# d_00_e_00.net
KiCad netlist of a schematic drawn in EasyEDA
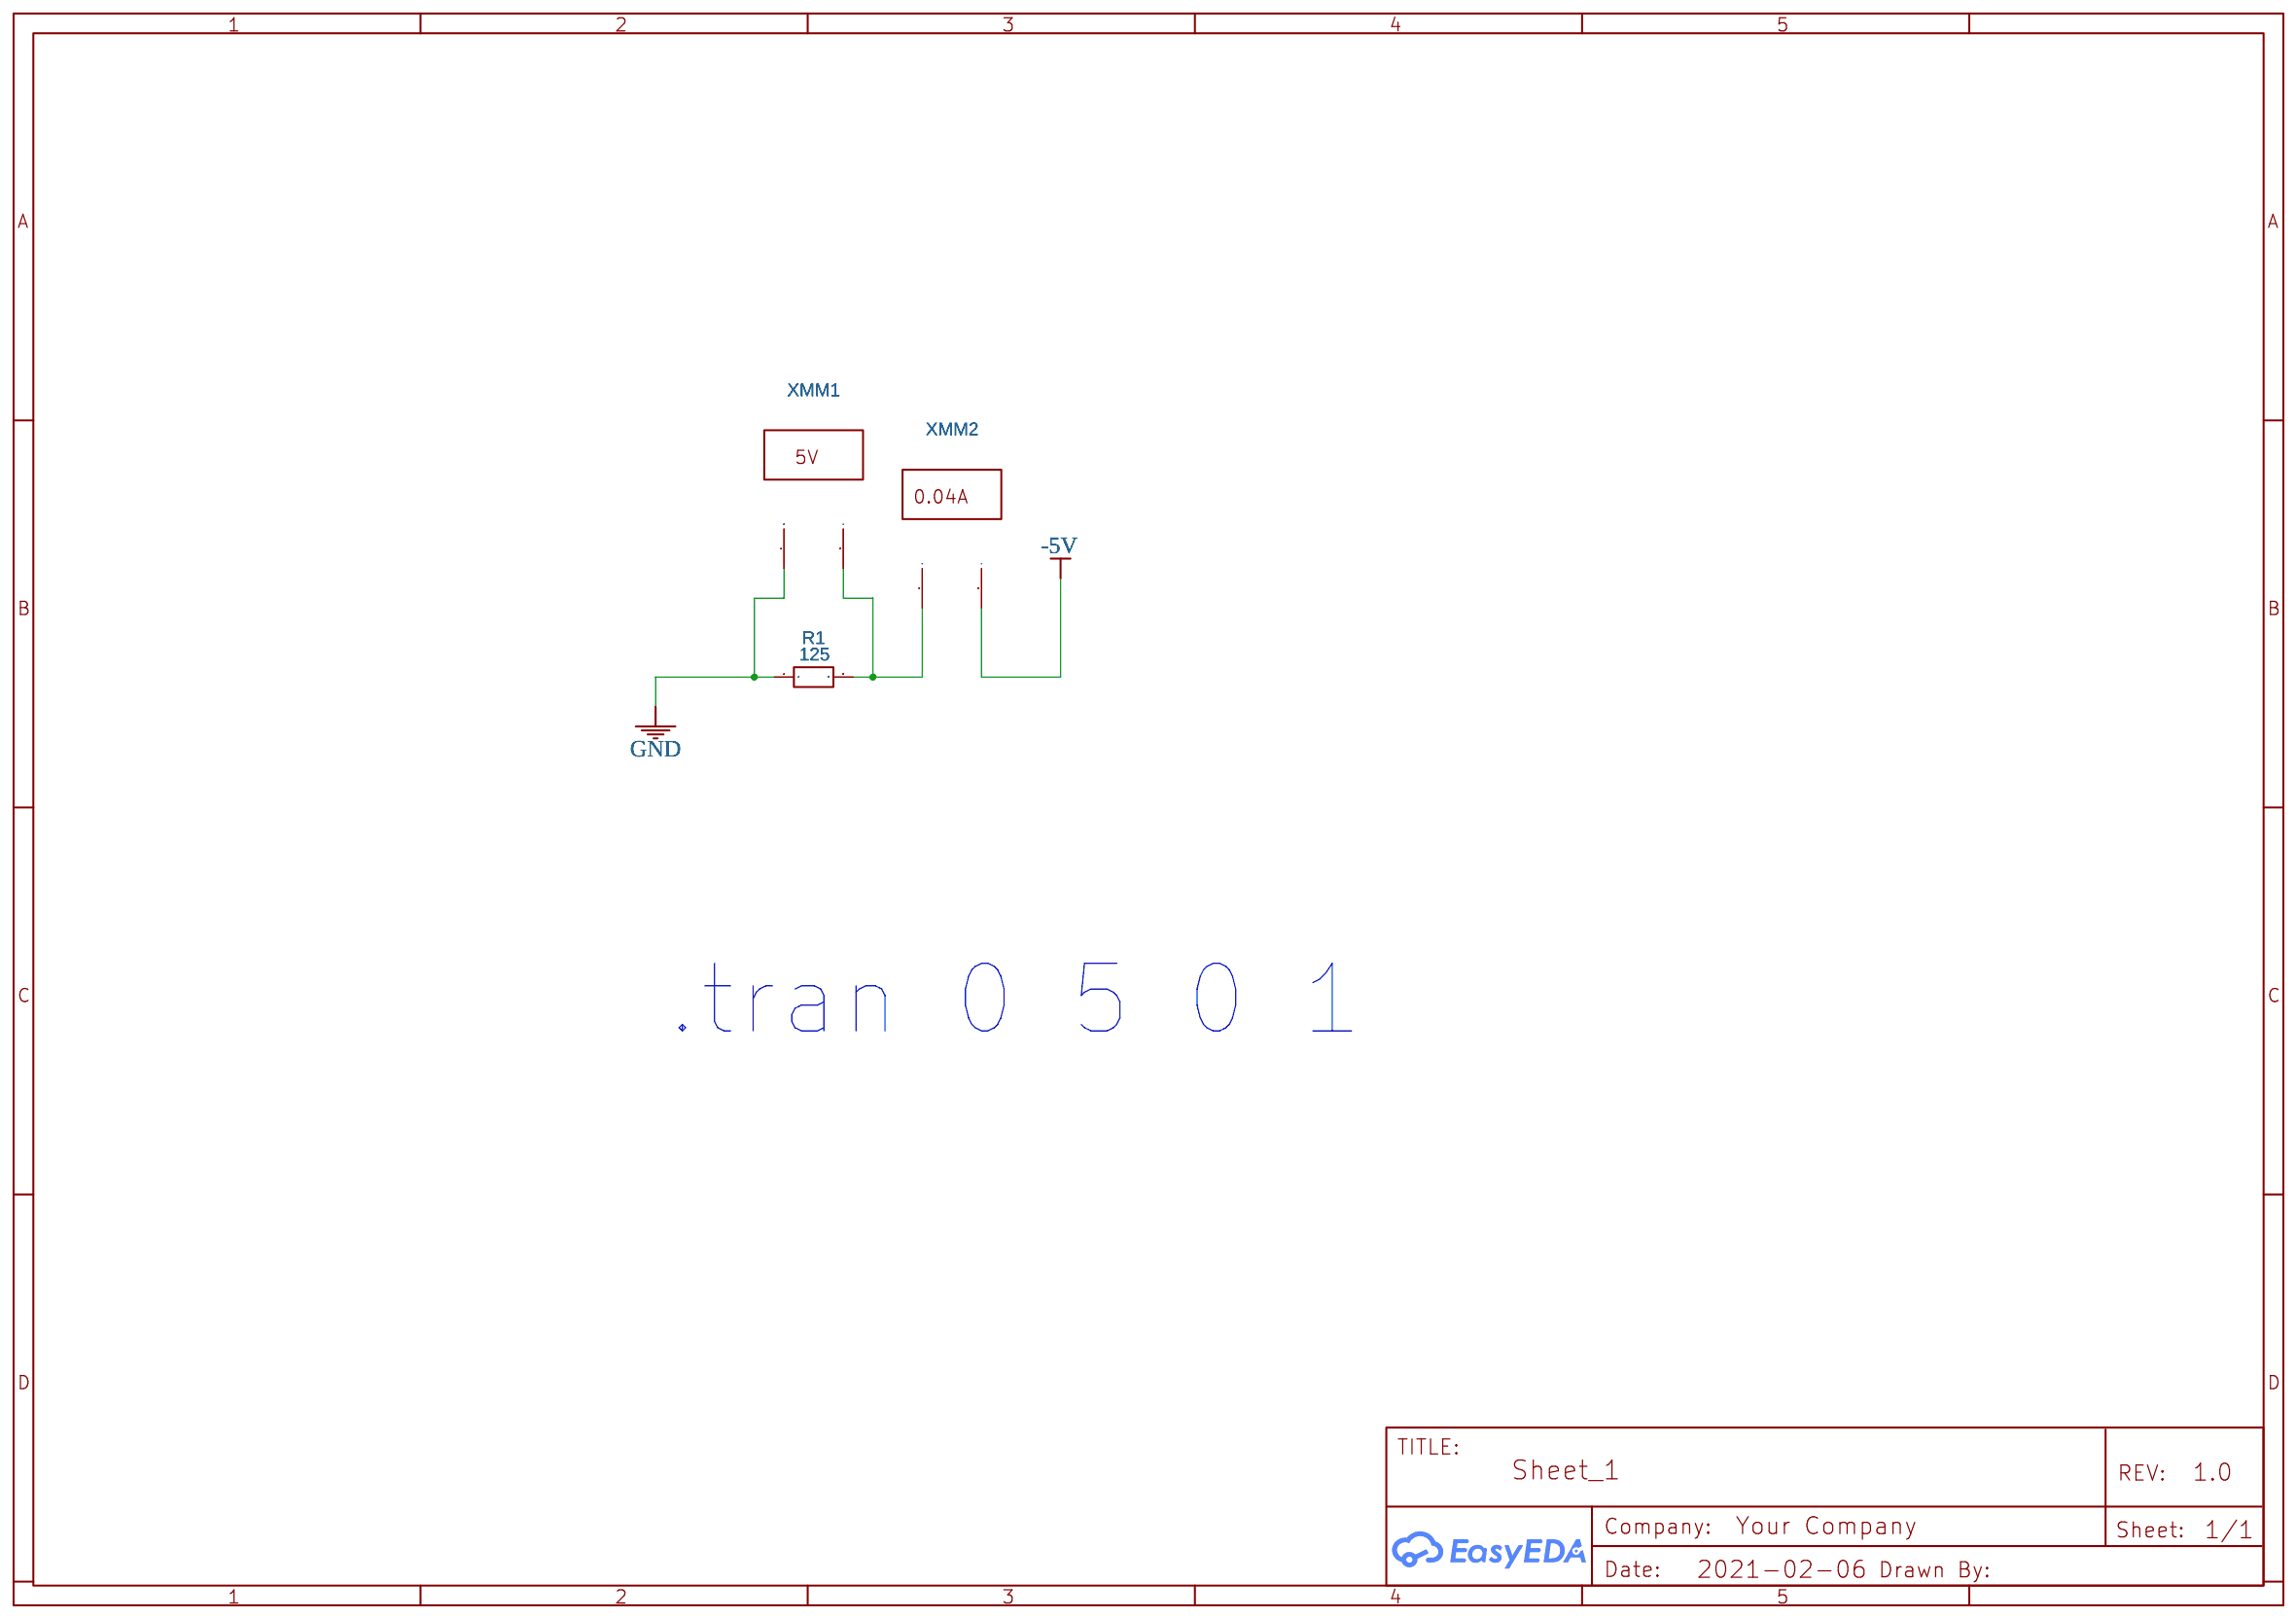
[diagram p0: schematic sheet]

(export (version "E")
  (design (tool "Eeschema 10.0.6"))
  (components
    (comp (ref "R1") (value "125") (libsource (lib "") (part "R_0603_EU")))
    (comp (ref "XMM1") (value "Multimeter") (libsource (lib "") (part "MULTIMETER")))
    (comp (ref "XMM2") (value "Multimeter") (libsource (lib "") (part "MULTIMETER_1")))
  )
  (nets
    (net (code "1") (name "-5V") (class "Default")
      (node (ref "XMM2") (pin "2") (pinfunction "I_2") (pintype "unspecified"))
    )
    (net (code "2") (name "GND") (class "Default")
      (node (ref "R1") (pin "1") (pinfunction "1_1") (pintype "unspecified"))
      (node (ref "XMM1") (pin "1") (pinfunction "+_1") (pintype "unspecified"))
    )
    (net (code "3") (name "Net-(XMM1-I)") (class "Default")
      (node (ref "R1") (pin "2") (pinfunction "2_2") (pintype "unspecified"))
      (node (ref "XMM1") (pin "2") (pinfunction "I_2") (pintype "unspecified"))
      (node (ref "XMM2") (pin "1") (pinfunction "+_1") (pintype "unspecified"))
    )
  )
)
